# USB_HS_PHY.net
KiCad netlist of a schematic drawn in Altium Designer
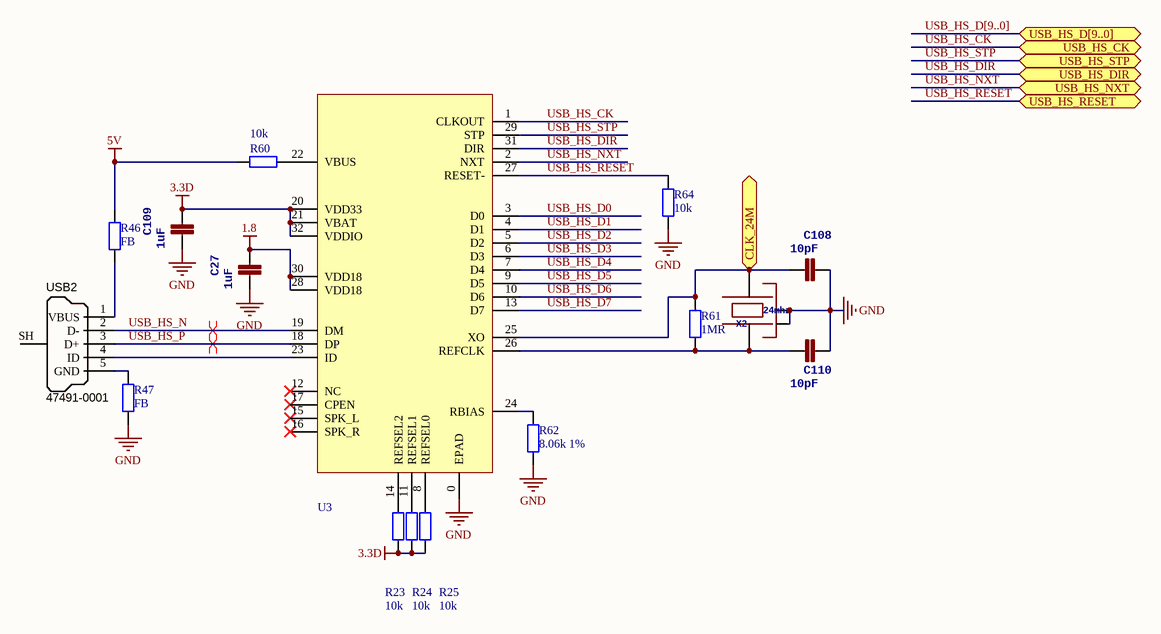
[diagram p0: USB_HS_PHY.SchDoc]

(export (version "E")
  (design (tool "Eeschema 10.0.6"))
  (components
    (comp (ref "C27")
      (value "1uF")
      (footprint "0402")
      (description "<b>Capacitor</b>\nStandard 0603 ceramic capacitor, and 0.1\" leaded capacitor.")
      (fields (field (name "PARTNO") "CC0402ZRY5V7BB104"))
      (libsource (lib "") (part "CAP0402-CAP_1"))
    )
    (comp (ref "C108")
      (value "10pF")
      (footprint "0402")
      (description "<b>Capacitor</b>\nStandard 0603 ceramic capacitor, and 0.1\" leaded capacitor.")
      (fields (field (name "PARTNO") "CC0402ZRY5V7BB104"))
      (libsource (lib "pixhawk2") (part "CAP0402-CAP"))
    )
    (comp (ref "C109")
      (value "1uF")
      (footprint "0402")
      (description "<b>Capacitor</b>\nStandard 0603 ceramic capacitor, and 0.1\" leaded capacitor.")
      (fields (field (name "PARTNO") "CC0402ZRY5V7BB104"))
      (libsource (lib "") (part "CAP0402-CAP_1"))
    )
    (comp (ref "C110")
      (value "10pF")
      (footprint "0402")
      (description "<b>Capacitor</b>\nStandard 0603 ceramic capacitor, and 0.1\" leaded capacitor.")
      (fields (field (name "PARTNO") "CC0402ZRY5V7BB104"))
      (libsource (lib "*") (part "CAP0402-CAP"))
    )
    (comp (ref "R23")
      (value "10k")
      (footprint "0402")
      (description "Resistor")
      (fields (field (name "PUBLISHER") "Altium Limited"))
      (libsource (lib "Miscellaneous Devices") (part "Res2"))
    )
    (comp (ref "R24")
      (value "10k")
      (footprint "0402")
      (description "Resistor")
      (fields (field (name "PUBLISHER") "Altium Limited"))
      (libsource (lib "Miscellaneous Devices") (part "Res2"))
    )
    (comp (ref "R25")
      (value "10k")
      (footprint "0402")
      (description "Resistor")
      (fields (field (name "PUBLISHER") "Altium Limited"))
      (libsource (lib "Miscellaneous Devices") (part "Res2"))
    )
    (comp (ref "R46")
      (value "FB")
      (footprint "0603")
      (description "Resistor")
      (fields (field (name "PUBLISHER") "Altium Limited"))
      (libsource (lib "Miscellaneous Devices") (part "Res2"))
    )
    (comp (ref "R47")
      (value "FB")
      (footprint "0603")
      (description "Resistor")
      (fields (field (name "PUBLISHER") "Altium Limited"))
      (libsource (lib "Miscellaneous Devices") (part "Res2"))
    )
    (comp (ref "R60")
      (value "10k")
      (footprint "0402")
      (description "Resistor")
      (fields (field (name "PUBLISHER") "Altium Limited"))
      (libsource (lib "") (part "Res2_1"))
    )
    (comp (ref "R61")
      (value "1MR")
      (footprint "0402")
      (description "Resistor")
      (fields (field (name "PUBLISHER") "Altium Limited"))
      (libsource (lib "") (part "Res2_2"))
    )
    (comp (ref "R62")
      (value "8.06k 1%")
      (footprint "0402")
      (description "Resistor")
      (fields (field (name "PUBLISHER") "Altium Limited"))
      (libsource (lib "") (part "Res2_2"))
    )
    (comp (ref "R64")
      (value "10k")
      (footprint "0402")
      (description "Resistor")
      (fields (field (name "PUBLISHER") "Altium Limited"))
      (libsource (lib "Miscellaneous Devices") (part "Res2"))
    )
    (comp (ref "U3") (value "USB3320") (footprint "USB3300") (libsource (lib "F4SDR") (part "USB3320")))
    (comp (ref "USB2")
      (value "USB Micro Type B")
      (footprint "MICRO-YZX")
      (description "Connector SMD USB Micro Type B middle mount")
      (fields (field (name "MANUFACTURER PART NUMBER 1") "47491-0001"))
      (libsource (lib "PBL - Connectors") (part "USB_Micro_TypeB"))
    )
    (comp (ref "X2")
      (value "24mhz")
      (footprint "OSCILLATOR-3.2X2.5")
      (description "Crystal Oscillator in 3.2x2.5 SMD")
      (libsource (lib "sch") (part "OSCILLATOR-3.2X2.5"))
    )
  )
  (nets
    (net (code "3") (name "/CLK_24M") (class "Default")
      (node (ref "C108") (pin "2") (pinfunction "2_2") (pintype "passive"))
      (node (ref "R61") (pin "2") (pinfunction "2_2") (pintype "passive"))
      (node (ref "U3") (pin "25") (pinfunction "XO_25") (pintype "passive"))
      (node (ref "X2") (pin "3") (pinfunction "3_3") (pintype "passive"))
    )
    (net (code "4") (name "/USB_HS_CK") (class "Default")
      (node (ref "U3") (pin "1") (pinfunction "CLKOUT_1") (pintype "passive"))
    )
    (net (code "5") (name "/USB_HS_D0") (class "Default")
      (node (ref "U3") (pin "3") (pinfunction "D0_3") (pintype "passive"))
    )
    (net (code "6") (name "/USB_HS_D1") (class "Default")
      (node (ref "U3") (pin "4") (pinfunction "D1_4") (pintype "passive"))
    )
    (net (code "7") (name "/USB_HS_D2") (class "Default")
      (node (ref "U3") (pin "5") (pinfunction "D2_5") (pintype "passive"))
    )
    (net (code "8") (name "/USB_HS_D3") (class "Default")
      (node (ref "U3") (pin "6") (pinfunction "D3_6") (pintype "passive"))
    )
    (net (code "9") (name "/USB_HS_D4") (class "Default")
      (node (ref "U3") (pin "7") (pinfunction "D4_7") (pintype "passive"))
    )
    (net (code "10") (name "/USB_HS_D5") (class "Default")
      (node (ref "U3") (pin "9") (pinfunction "D5_9") (pintype "passive"))
    )
    (net (code "11") (name "/USB_HS_D6") (class "Default")
      (node (ref "U3") (pin "10") (pinfunction "D6_10") (pintype "passive"))
    )
    (net (code "12") (name "/USB_HS_D7") (class "Default")
      (node (ref "U3") (pin "13") (pinfunction "D7_13") (pintype "passive"))
    )
    (net (code "13") (name "/USB_HS_DIR") (class "Default")
      (node (ref "U3") (pin "31") (pinfunction "DIR_31") (pintype "passive"))
    )
    (net (code "15") (name "/USB_HS_N") (class "Default")
      (node (ref "U3") (pin "19") (pinfunction "DM_19") (pintype "passive"))
      (node (ref "USB2") (pin "2") (pinfunction "D-_2") (pintype "passive"))
    )
    (net (code "16") (name "/USB_HS_NXT") (class "Default")
      (node (ref "U3") (pin "2") (pinfunction "NXT_2") (pintype "passive"))
    )
    (net (code "17") (name "/USB_HS_P") (class "Default")
      (node (ref "U3") (pin "18") (pinfunction "DP_18") (pintype "passive"))
      (node (ref "USB2") (pin "3") (pinfunction "D+_3") (pintype "passive"))
    )
    (net (code "18") (name "/USB_HS_RESET") (class "Default")
      (node (ref "R64") (pin "1") (pinfunction "1_1") (pintype "passive"))
      (node (ref "U3") (pin "27") (pinfunction "RESET-_27") (pintype "passive"))
    )
    (net (code "19") (name "/USB_HS_STP") (class "Default")
      (node (ref "U3") (pin "29") (pinfunction "STP_29") (pintype "passive"))
    )
    (net (code "20") (name "1.8") (class "Default")
      (node (ref "C27") (pin "1") (pinfunction "1_1") (pintype "passive"))
      (node (ref "U3") (pin "28") (pinfunction "VDD18_28") (pintype "passive"))
      (node (ref "U3") (pin "30") (pinfunction "VDD18_30") (pintype "passive"))
    )
    (net (code "21") (name "3.3D") (class "Default")
      (node (ref "C109") (pin "1") (pinfunction "1_1") (pintype "passive"))
      (node (ref "R23") (pin "2") (pinfunction "2_2") (pintype "passive"))
      (node (ref "R24") (pin "2") (pinfunction "2_2") (pintype "passive"))
      (node (ref "R25") (pin "2") (pinfunction "2_2") (pintype "passive"))
      (node (ref "U3") (pin "20") (pinfunction "VDD33_20") (pintype "passive"))
      (node (ref "U3") (pin "21") (pinfunction "VBAT_21") (pintype "passive"))
      (node (ref "U3") (pin "32") (pinfunction "VDDIO_32") (pintype "passive"))
    )
    (net (code "22") (name "5V") (class "Default")
      (node (ref "R46") (pin "1") (pinfunction "1_1") (pintype "passive"))
      (node (ref "R60") (pin "1") (pinfunction "1_1") (pintype "passive"))
    )
    (net (code "23") (name "GND") (class "Default")
      (node (ref "C108") (pin "1") (pinfunction "1_1") (pintype "passive"))
      (node (ref "C109") (pin "2") (pinfunction "2_2") (pintype "passive"))
      (node (ref "C110") (pin "1") (pinfunction "1_1") (pintype "passive"))
      (node (ref "C27") (pin "2") (pinfunction "2_2") (pintype "passive"))
      (node (ref "R47") (pin "2") (pinfunction "2_2") (pintype "passive"))
      (node (ref "R62") (pin "1") (pinfunction "1_1") (pintype "passive"))
      (node (ref "R64") (pin "2") (pinfunction "2_2") (pintype "passive"))
      (node (ref "U3") (pin "0") (pinfunction "EPAD_0") (pintype "passive"))
      (node (ref "X2") (pin "2") (pinfunction "NC_2_2") (pintype "open_emitter"))
      (node (ref "X2") (pin "4") (pinfunction "NC_4_4") (pintype "open_emitter"))
    )
    (net (code "24") (name "Net-(U3-ID)") (class "Default")
      (node (ref "U3") (pin "23") (pinfunction "ID_23") (pintype "passive"))
      (node (ref "USB2") (pin "4") (pinfunction "ID_4") (pintype "passive"))
    )
    (net (code "25") (name "Net-(U3-RBIAS)") (class "Default")
      (node (ref "R62") (pin "2") (pinfunction "2_2") (pintype "passive"))
      (node (ref "U3") (pin "24") (pinfunction "RBIAS_24") (pintype "passive"))
    )
    (net (code "26") (name "Net-(U3-REFCLK)") (class "Default")
      (node (ref "C110") (pin "2") (pinfunction "2_2") (pintype "passive"))
      (node (ref "R61") (pin "1") (pinfunction "1_1") (pintype "passive"))
      (node (ref "U3") (pin "26") (pinfunction "REFCLK_26") (pintype "passive"))
      (node (ref "X2") (pin "1") (pinfunction "1_1") (pintype "passive"))
    )
    (net (code "27") (name "Net-(U3-REFSEL0)") (class "Default")
      (node (ref "R25") (pin "1") (pinfunction "1_1") (pintype "passive"))
      (node (ref "U3") (pin "8") (pinfunction "REFSEL0_8") (pintype "passive"))
    )
    (net (code "28") (name "Net-(U3-REFSEL1)") (class "Default")
      (node (ref "R24") (pin "1") (pinfunction "1_1") (pintype "passive"))
      (node (ref "U3") (pin "11") (pinfunction "REFSEL1_11") (pintype "passive"))
    )
    (net (code "29") (name "Net-(U3-REFSEL2)") (class "Default")
      (node (ref "R23") (pin "1") (pinfunction "1_1") (pintype "passive"))
      (node (ref "U3") (pin "14") (pinfunction "REFSEL2_14") (pintype "passive"))
    )
    (net (code "30") (name "Net-(U3-VBUS)") (class "Default")
      (node (ref "R60") (pin "2") (pinfunction "2_2") (pintype "passive"))
      (node (ref "U3") (pin "22") (pinfunction "VBUS_22") (pintype "passive"))
    )
    (net (code "31") (name "Net-(USB2-GND)") (class "Default")
      (node (ref "R47") (pin "1") (pinfunction "1_1") (pintype "passive"))
      (node (ref "USB2") (pin "5") (pinfunction "GND_5") (pintype "passive"))
    )
    (net (code "32") (name "Net-(USB2-VBUS)") (class "Default")
      (node (ref "R46") (pin "2") (pinfunction "2_2") (pintype "passive"))
      (node (ref "USB2") (pin "1") (pinfunction "VBUS_1") (pintype "passive"))
    )
    (net (code "33") (name "unconnected-(U3-CPEN-Pad17)") (class "Default")
      (node (ref "U3") (pin "17") (pinfunction "CPEN_17") (pintype "passive+no_connect"))
    )
    (net (code "34") (name "unconnected-(U3-NC-Pad12)") (class "Default")
      (node (ref "U3") (pin "12") (pinfunction "NC_12") (pintype "passive+no_connect"))
    )
    (net (code "35") (name "unconnected-(U3-SPK_L-Pad15)") (class "Default")
      (node (ref "U3") (pin "15") (pinfunction "SPK_L_15") (pintype "passive+no_connect"))
    )
    (net (code "36") (name "unconnected-(U3-SPK_R-Pad16)") (class "Default")
      (node (ref "U3") (pin "16") (pinfunction "SPK_R_16") (pintype "passive+no_connect"))
    )
    (net (code "37") (name "unconnected-(USB2-Shell-PadSH)") (class "Default")
      (node (ref "USB2") (pin "SH") (pinfunction "Shell_SH") (pintype "passive"))
    )
  )
)
